# SRAM_MODULE_2_0a.net
KiCad netlist of a schematic drawn in EAGLE
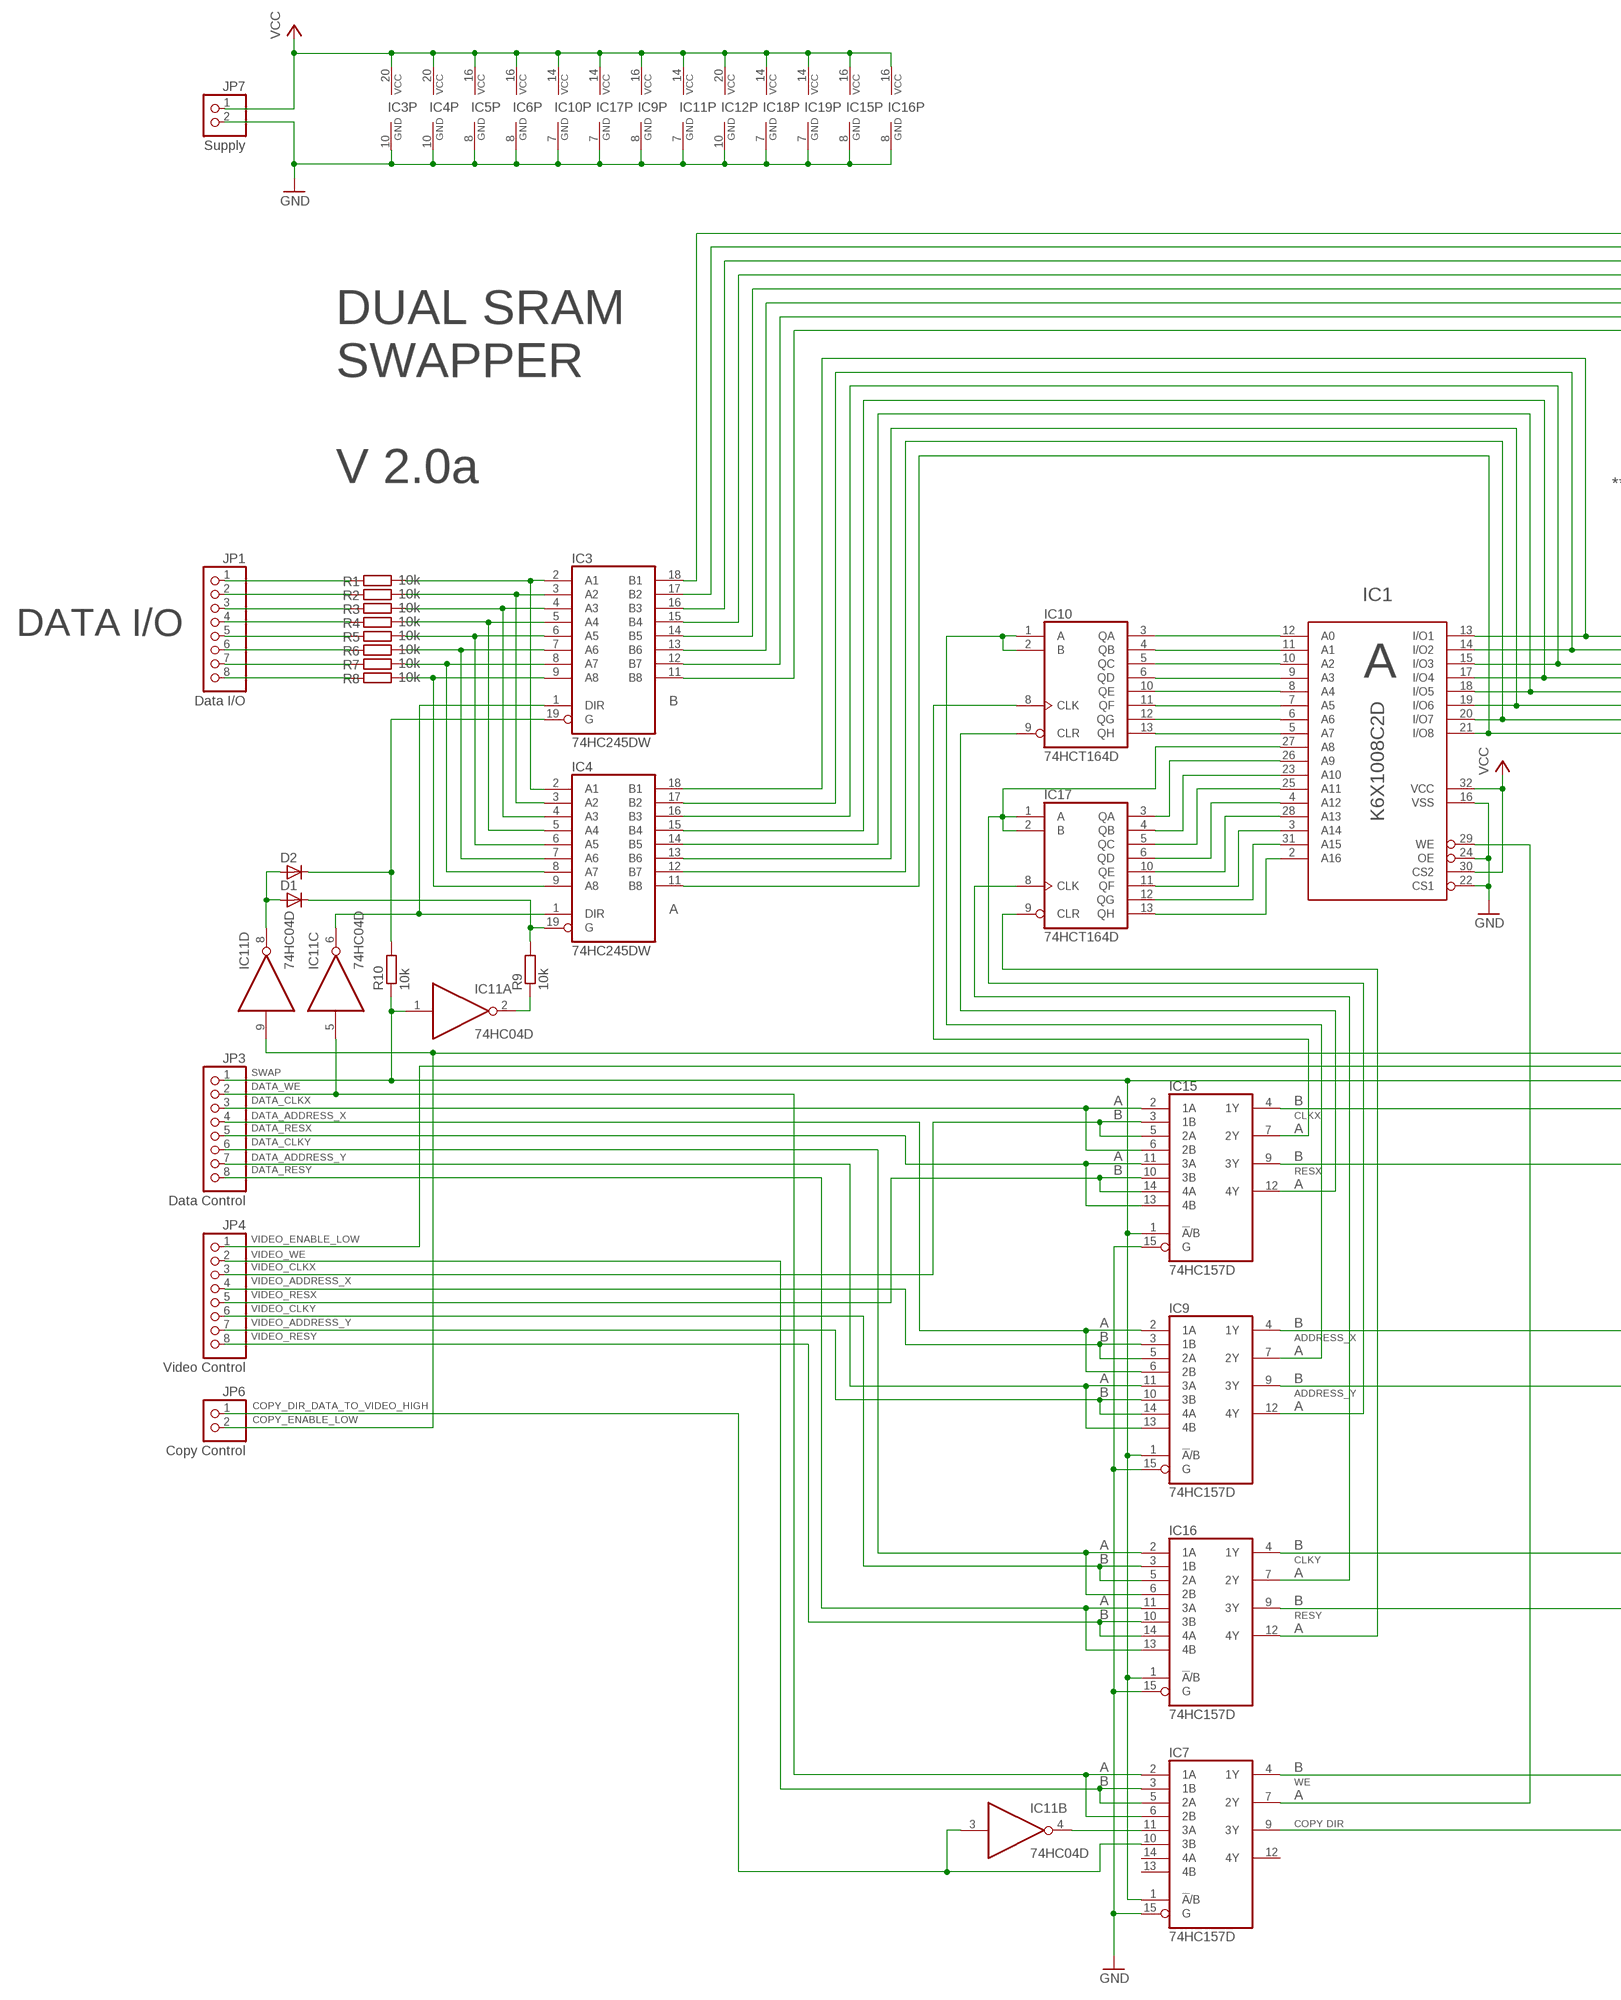
[diagram p0: schematic, sheet 1, part 1 of 2]
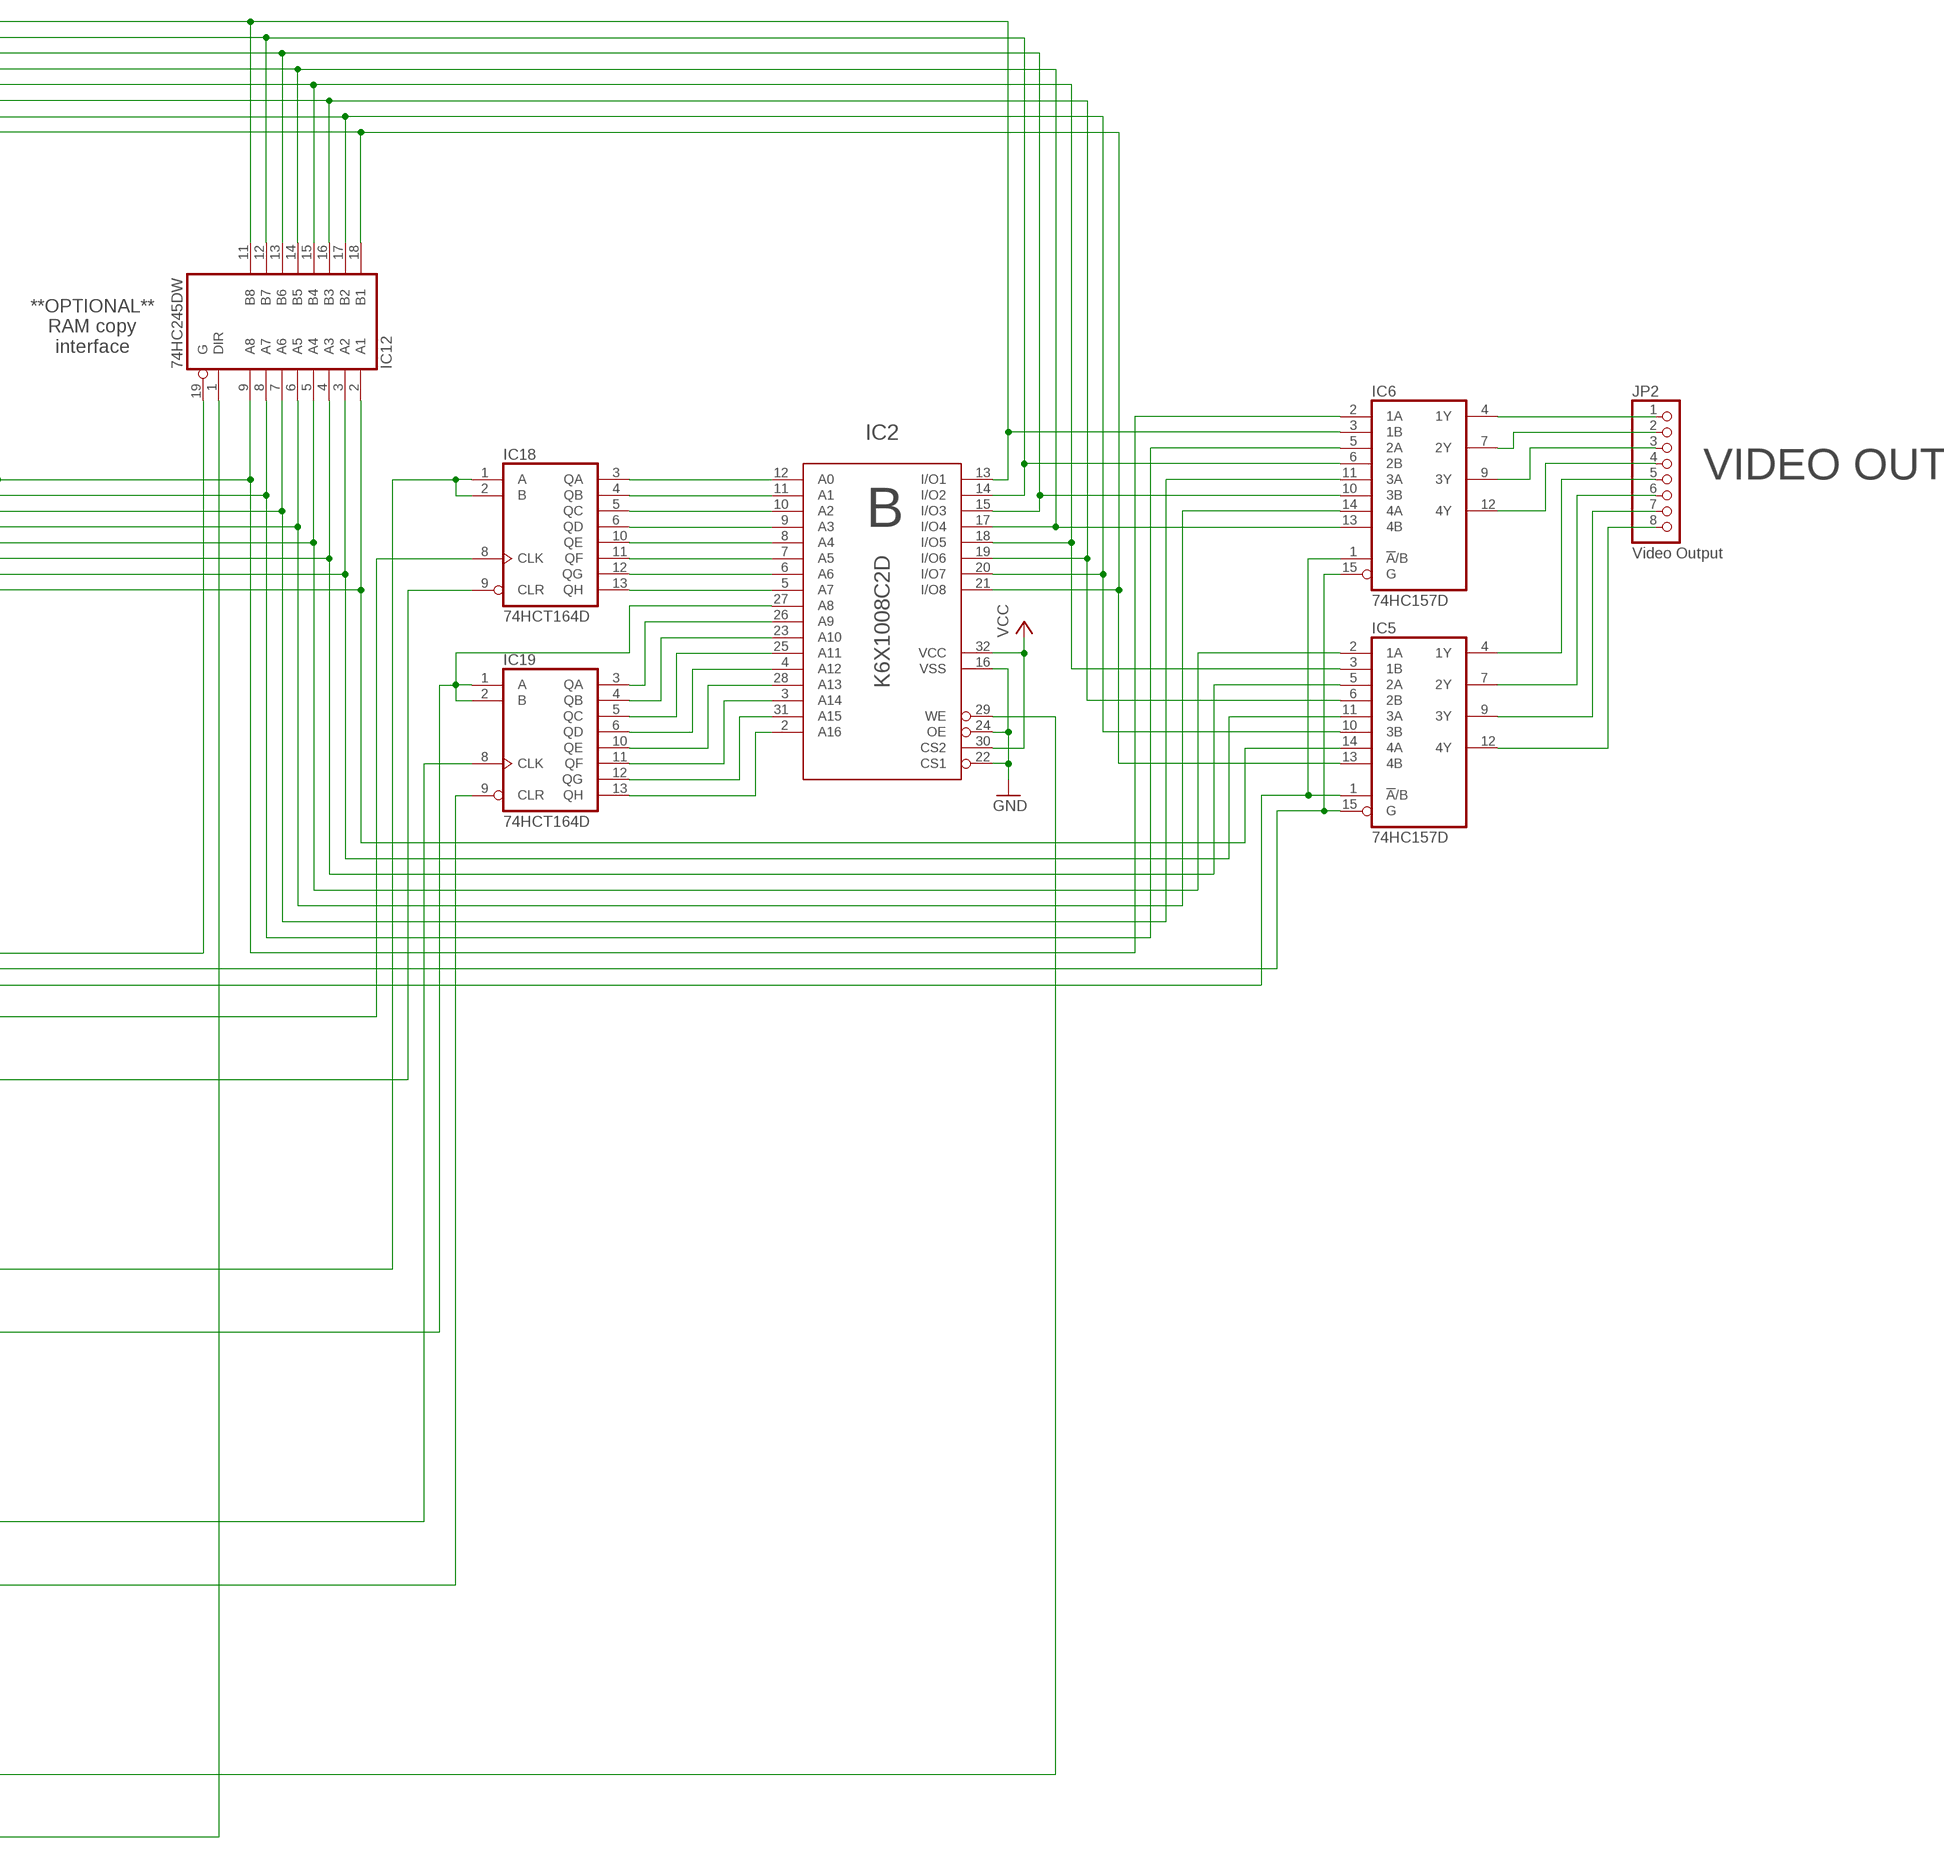
[diagram p1: schematic, sheet 1, part 2 of 2]

(export (version "E")
  (design (tool "Eeschema 10.0.6"))
  (components
    (comp (ref "D1")
      (value "D-A1-C3")
      (footprint "eagle-import:SOT23")
      (libsource (lib "eagle-import") (part "D-A1-C3"))
    )
    (comp (ref "D2")
      (value "D-A1-C3")
      (footprint "eagle-import:SOT23")
      (libsource (lib "eagle-import") (part "D-A1-C3"))
    )
    (comp (ref "IC1")
      (value "K6X1008C2D")
      (footprint "eagle-import:SOP32-5")
      (libsource (lib "eagle-import") (part "K6X1008C2D"))
    )
    (comp (ref "IC2")
      (value "K6X1008C2D")
      (footprint "eagle-import:SOP32-5")
      (libsource (lib "eagle-import") (part "K6X1008C2D"))
    )
    (comp (ref "IC3")
      (value "74HC245DW")
      (footprint "eagle-import:SO20W")
      (libsource (lib "eagle-import") (part "74245DWHC"))
    )
    (comp (ref "IC4")
      (value "74HC245DW")
      (footprint "eagle-import:SO20W")
      (libsource (lib "eagle-import") (part "74245DWHC"))
    )
    (comp (ref "IC5")
      (value "74HC157D")
      (footprint "eagle-import:SO16")
      (libsource (lib "eagle-import") (part "74157DHC"))
    )
    (comp (ref "IC6")
      (value "74HC157D")
      (footprint "eagle-import:SO16")
      (libsource (lib "eagle-import") (part "74157DHC"))
    )
    (comp (ref "IC7")
      (value "74HC157D")
      (footprint "eagle-import:SO16")
      (libsource (lib "eagle-import") (part "74157DHC"))
    )
    (comp (ref "IC9")
      (value "74HC157D")
      (footprint "eagle-import:SO16")
      (libsource (lib "eagle-import") (part "74157DHC"))
    )
    (comp (ref "IC10")
      (value "74HCT164D")
      (footprint "eagle-import:SO14")
      (libsource (lib "eagle-import") (part "74164DHCT"))
    )
    (comp (ref "IC11")
      (value "74HC04D")
      (footprint "eagle-import:SO14")
      (libsource (lib "eagle-import") (part "7404DHC"))
    )
    (comp (ref "IC12")
      (value "74HC245DW")
      (footprint "eagle-import:SO20W")
      (libsource (lib "eagle-import") (part "74245DWHC"))
    )
    (comp (ref "IC15")
      (value "74HC157D")
      (footprint "eagle-import:SO16")
      (libsource (lib "eagle-import") (part "74157DHC"))
    )
    (comp (ref "IC16")
      (value "74HC157D")
      (footprint "eagle-import:SO16")
      (libsource (lib "eagle-import") (part "74157DHC"))
    )
    (comp (ref "IC17")
      (value "74HCT164D")
      (footprint "eagle-import:SO14")
      (libsource (lib "eagle-import") (part "74164DHCT"))
    )
    (comp (ref "IC18")
      (value "74HCT164D")
      (footprint "eagle-import:SO14")
      (libsource (lib "eagle-import") (part "74164DHCT"))
    )
    (comp (ref "IC19")
      (value "74HCT164D")
      (footprint "eagle-import:SO14")
      (libsource (lib "eagle-import") (part "74164DHCT"))
    )
    (comp (ref "JP1")
      (value "Data I/O")
      (footprint "eagle-import:1X08")
      (libsource (lib "eagle-import") (part "PINHD-1X8"))
    )
    (comp (ref "JP2")
      (value "Video Output")
      (footprint "eagle-import:1X08")
      (libsource (lib "eagle-import") (part "PINHD-1X8"))
    )
    (comp (ref "JP3")
      (value "Data Control")
      (footprint "eagle-import:1X08")
      (libsource (lib "eagle-import") (part "PINHD-1X8"))
    )
    (comp (ref "JP4")
      (value "Video Control")
      (footprint "eagle-import:1X08")
      (libsource (lib "eagle-import") (part "PINHD-1X8"))
    )
    (comp (ref "JP6")
      (value "Copy Control")
      (footprint "eagle-import:1X02")
      (libsource (lib "eagle-import") (part "PINHD-1X2"))
    )
    (comp (ref "JP7")
      (value "Supply")
      (footprint "eagle-import:1X02")
      (libsource (lib "eagle-import") (part "PINHD-1X2"))
    )
    (comp (ref "R1")
      (value "10k")
      (footprint "eagle-import:R0603")
      (libsource (lib "eagle-import") (part "R-EU_R0603"))
    )
    (comp (ref "R2")
      (value "10k")
      (footprint "eagle-import:R0603")
      (libsource (lib "eagle-import") (part "R-EU_R0603"))
    )
    (comp (ref "R3")
      (value "10k")
      (footprint "eagle-import:R0603")
      (libsource (lib "eagle-import") (part "R-EU_R0603"))
    )
    (comp (ref "R4")
      (value "10k")
      (footprint "eagle-import:R0603")
      (libsource (lib "eagle-import") (part "R-EU_R0603"))
    )
    (comp (ref "R5")
      (value "10k")
      (footprint "eagle-import:R0603")
      (libsource (lib "eagle-import") (part "R-EU_R0603"))
    )
    (comp (ref "R6")
      (value "10k")
      (footprint "eagle-import:R0603")
      (libsource (lib "eagle-import") (part "R-EU_R0603"))
    )
    (comp (ref "R7")
      (value "10k")
      (footprint "eagle-import:R0603")
      (libsource (lib "eagle-import") (part "R-EU_R0603"))
    )
    (comp (ref "R8")
      (value "10k")
      (footprint "eagle-import:R0603")
      (libsource (lib "eagle-import") (part "R-EU_R0603"))
    )
    (comp (ref "R9")
      (value "10k")
      (footprint "eagle-import:R0603")
      (libsource (lib "eagle-import") (part "R-EU_R0603"))
    )
    (comp (ref "R10")
      (value "10k")
      (footprint "eagle-import:R0603")
      (libsource (lib "eagle-import") (part "R-EU_R0603"))
    )
  )
  (nets
    (net (code "1") (name "/COPY_DIR_DATA_TO_VIDEO_HIGH") (class "Default")
      (node (ref "IC11") (pin "3") (pinfunction "I_3") (pintype "input"))
      (node (ref "IC7") (pin "10") (pinfunction "3B_10") (pintype "input"))
      (node (ref "JP6") (pin "1") (pinfunction "1_1") (pintype "passive"))
    )
    (net (code "2") (name "/COPY_ENABLE_LOW") (class "Default")
      (node (ref "IC11") (pin "9") (pinfunction "I_9") (pintype "input"))
      (node (ref "IC12") (pin "19") (pinfunction "G_19") (pintype "input"))
      (node (ref "JP6") (pin "2") (pinfunction "2_2") (pintype "passive"))
    )
    (net (code "3") (name "/DATA_ADDRESS_X") (class "Default")
      (node (ref "IC9") (pin "2") (pinfunction "1A_2") (pintype "input"))
      (node (ref "IC9") (pin "6") (pinfunction "2B_6") (pintype "input"))
      (node (ref "JP3") (pin "4") (pinfunction "4_4") (pintype "passive"))
    )
    (net (code "4") (name "/DATA_ADDRESS_Y") (class "Default")
      (node (ref "IC9") (pin "11") (pinfunction "3A_11") (pintype "input"))
      (node (ref "IC9") (pin "13") (pinfunction "4B_13") (pintype "input"))
      (node (ref "JP3") (pin "7") (pinfunction "7_7") (pintype "passive"))
    )
    (net (code "5") (name "/DATA_CLKX") (class "Default")
      (node (ref "IC15") (pin "2") (pinfunction "1A_2") (pintype "input"))
      (node (ref "IC15") (pin "6") (pinfunction "2B_6") (pintype "input"))
      (node (ref "JP3") (pin "3") (pinfunction "3_3") (pintype "passive"))
    )
    (net (code "6") (name "/DATA_CLKY") (class "Default")
      (node (ref "IC16") (pin "2") (pinfunction "1A_2") (pintype "input"))
      (node (ref "IC16") (pin "6") (pinfunction "2B_6") (pintype "input"))
      (node (ref "JP3") (pin "6") (pinfunction "6_6") (pintype "passive"))
    )
    (net (code "7") (name "/DATA_RESX") (class "Default")
      (node (ref "IC15") (pin "11") (pinfunction "3A_11") (pintype "input"))
      (node (ref "IC15") (pin "13") (pinfunction "4B_13") (pintype "input"))
      (node (ref "JP3") (pin "5") (pinfunction "5_5") (pintype "passive"))
    )
    (net (code "8") (name "/DATA_RESY") (class "Default")
      (node (ref "IC16") (pin "11") (pinfunction "3A_11") (pintype "input"))
      (node (ref "IC16") (pin "13") (pinfunction "4B_13") (pintype "input"))
      (node (ref "JP3") (pin "8") (pinfunction "8_8") (pintype "passive"))
    )
    (net (code "9") (name "/DATA_WE") (class "Default")
      (node (ref "IC11") (pin "5") (pinfunction "I_5") (pintype "input"))
      (node (ref "IC7") (pin "2") (pinfunction "1A_2") (pintype "input"))
      (node (ref "IC7") (pin "6") (pinfunction "2B_6") (pintype "input"))
      (node (ref "JP3") (pin "2") (pinfunction "2_2") (pintype "passive"))
    )
    (net (code "10") (name "/SWAP") (class "Default")
      (node (ref "IC11") (pin "1") (pinfunction "I_1") (pintype "input"))
      (node (ref "IC15") (pin "1") (pinfunction "~{A}/B_1") (pintype "input"))
      (node (ref "IC16") (pin "1") (pinfunction "~{A}/B_1") (pintype "input"))
      (node (ref "IC5") (pin "1") (pinfunction "~{A}/B_1") (pintype "input"))
      (node (ref "IC6") (pin "1") (pinfunction "~{A}/B_1") (pintype "input"))
      (node (ref "IC7") (pin "1") (pinfunction "~{A}/B_1") (pintype "input"))
      (node (ref "IC9") (pin "1") (pinfunction "~{A}/B_1") (pintype "input"))
      (node (ref "JP3") (pin "1") (pinfunction "1_1") (pintype "passive"))
      (node (ref "R10") (pin "1") (pinfunction "1_1") (pintype "passive"))
    )
    (net (code "11") (name "/VIDEO_ADDRESS_X") (class "Default")
      (node (ref "IC9") (pin "3") (pinfunction "1B_3") (pintype "input"))
      (node (ref "IC9") (pin "5") (pinfunction "2A_5") (pintype "input"))
      (node (ref "JP4") (pin "4") (pinfunction "4_4") (pintype "passive"))
    )
    (net (code "12") (name "/VIDEO_ADDRESS_Y") (class "Default")
      (node (ref "IC9") (pin "10") (pinfunction "3B_10") (pintype "input"))
      (node (ref "IC9") (pin "14") (pinfunction "4A_14") (pintype "input"))
      (node (ref "JP4") (pin "7") (pinfunction "7_7") (pintype "passive"))
    )
    (net (code "13") (name "/VIDEO_CLKX") (class "Default")
      (node (ref "IC15") (pin "3") (pinfunction "1B_3") (pintype "input"))
      (node (ref "IC15") (pin "5") (pinfunction "2A_5") (pintype "input"))
      (node (ref "JP4") (pin "3") (pinfunction "3_3") (pintype "passive"))
    )
    (net (code "14") (name "/VIDEO_CLKY") (class "Default")
      (node (ref "IC16") (pin "3") (pinfunction "1B_3") (pintype "input"))
      (node (ref "IC16") (pin "5") (pinfunction "2A_5") (pintype "input"))
      (node (ref "JP4") (pin "6") (pinfunction "6_6") (pintype "passive"))
    )
    (net (code "15") (name "/VIDEO_ENABLE_LOW") (class "Default")
      (node (ref "IC5") (pin "15") (pinfunction "G_15") (pintype "input"))
      (node (ref "IC6") (pin "15") (pinfunction "G_15") (pintype "input"))
      (node (ref "JP4") (pin "1") (pinfunction "1_1") (pintype "passive"))
    )
    (net (code "16") (name "/VIDEO_RESX") (class "Default")
      (node (ref "IC15") (pin "10") (pinfunction "3B_10") (pintype "input"))
      (node (ref "IC15") (pin "14") (pinfunction "4A_14") (pintype "input"))
      (node (ref "JP4") (pin "5") (pinfunction "5_5") (pintype "passive"))
    )
    (net (code "17") (name "/VIDEO_RESY") (class "Default")
      (node (ref "IC16") (pin "10") (pinfunction "3B_10") (pintype "input"))
      (node (ref "IC16") (pin "14") (pinfunction "4A_14") (pintype "input"))
      (node (ref "JP4") (pin "8") (pinfunction "8_8") (pintype "passive"))
    )
    (net (code "18") (name "/VIDEO_WE") (class "Default")
      (node (ref "IC7") (pin "3") (pinfunction "1B_3") (pintype "input"))
      (node (ref "IC7") (pin "5") (pinfunction "2A_5") (pintype "input"))
      (node (ref "JP4") (pin "2") (pinfunction "2_2") (pintype "passive"))
    )
    (net (code "19") (name "GND") (class "Default")
      (node (ref "IC1") (pin "16") (pinfunction "VSS_16") (pintype "power_in"))
      (node (ref "IC1") (pin "22") (pinfunction "CS1_22") (pintype "input"))
      (node (ref "IC1") (pin "24") (pinfunction "OE_24") (pintype "input"))
      (node (ref "IC10") (pin "7") (pinfunction "GND_7") (pintype "power_in"))
      (node (ref "IC11") (pin "7") (pinfunction "GND_7") (pintype "power_in"))
      (node (ref "IC12") (pin "10") (pinfunction "GND_10") (pintype "power_in"))
      (node (ref "IC15") (pin "15") (pinfunction "G_15") (pintype "input"))
      (node (ref "IC15") (pin "8") (pinfunction "GND_8") (pintype "power_in"))
      (node (ref "IC16") (pin "15") (pinfunction "G_15") (pintype "input"))
      (node (ref "IC16") (pin "8") (pinfunction "GND_8") (pintype "power_in"))
      (node (ref "IC17") (pin "7") (pinfunction "GND_7") (pintype "power_in"))
      (node (ref "IC18") (pin "7") (pinfunction "GND_7") (pintype "power_in"))
      (node (ref "IC19") (pin "7") (pinfunction "GND_7") (pintype "power_in"))
      (node (ref "IC2") (pin "16") (pinfunction "VSS_16") (pintype "power_in"))
      (node (ref "IC2") (pin "22") (pinfunction "CS1_22") (pintype "input"))
      (node (ref "IC2") (pin "24") (pinfunction "OE_24") (pintype "input"))
      (node (ref "IC3") (pin "10") (pinfunction "GND_10") (pintype "power_in"))
      (node (ref "IC4") (pin "10") (pinfunction "GND_10") (pintype "power_in"))
      (node (ref "IC5") (pin "8") (pinfunction "GND_8") (pintype "power_in"))
      (node (ref "IC6") (pin "8") (pinfunction "GND_8") (pintype "power_in"))
      (node (ref "IC7") (pin "15") (pinfunction "G_15") (pintype "input"))
      (node (ref "IC9") (pin "15") (pinfunction "G_15") (pintype "input"))
      (node (ref "IC9") (pin "8") (pinfunction "GND_8") (pintype "power_in"))
      (node (ref "JP7") (pin "2") (pinfunction "2_2") (pintype "passive"))
    )
    (net (code "20") (name "Net-(D1-A)") (class "Default")
      (node (ref "D1") (pin "1") (pinfunction "A_1") (pintype "passive"))
      (node (ref "D2") (pin "1") (pinfunction "A_1") (pintype "passive"))
      (node (ref "IC11") (pin "8") (pinfunction "O_8") (pintype "output"))
    )
    (net (code "21") (name "Net-(D1-C)") (class "Default")
      (node (ref "D1") (pin "3") (pinfunction "C_3") (pintype "passive"))
      (node (ref "IC4") (pin "19") (pinfunction "G_19") (pintype "input"))
      (node (ref "R9") (pin "2") (pinfunction "2_2") (pintype "passive"))
    )
    (net (code "22") (name "Net-(D2-C)") (class "Default")
      (node (ref "D2") (pin "3") (pinfunction "C_3") (pintype "passive"))
      (node (ref "IC3") (pin "19") (pinfunction "G_19") (pintype "input"))
      (node (ref "R10") (pin "2") (pinfunction "2_2") (pintype "passive"))
    )
    (net (code "23") (name "Net-(IC1-A0)") (class "Default")
      (node (ref "IC1") (pin "12") (pinfunction "A0_12") (pintype "input"))
      (node (ref "IC10") (pin "3") (pinfunction "QA_3") (pintype "output"))
    )
    (net (code "24") (name "Net-(IC1-A1)") (class "Default")
      (node (ref "IC1") (pin "11") (pinfunction "A1_11") (pintype "input"))
      (node (ref "IC10") (pin "4") (pinfunction "QB_4") (pintype "output"))
    )
    (net (code "25") (name "Net-(IC1-A2)") (class "Default")
      (node (ref "IC1") (pin "10") (pinfunction "A2_10") (pintype "input"))
      (node (ref "IC10") (pin "5") (pinfunction "QC_5") (pintype "output"))
    )
    (net (code "26") (name "Net-(IC1-A3)") (class "Default")
      (node (ref "IC1") (pin "9") (pinfunction "A3_9") (pintype "input"))
      (node (ref "IC10") (pin "6") (pinfunction "QD_6") (pintype "output"))
    )
    (net (code "27") (name "Net-(IC1-A4)") (class "Default")
      (node (ref "IC1") (pin "8") (pinfunction "A4_8") (pintype "input"))
      (node (ref "IC10") (pin "10") (pinfunction "QE_10") (pintype "output"))
    )
    (net (code "28") (name "Net-(IC1-A5)") (class "Default")
      (node (ref "IC1") (pin "7") (pinfunction "A5_7") (pintype "input"))
      (node (ref "IC10") (pin "11") (pinfunction "QF_11") (pintype "output"))
    )
    (net (code "29") (name "Net-(IC1-A6)") (class "Default")
      (node (ref "IC1") (pin "6") (pinfunction "A6_6") (pintype "input"))
      (node (ref "IC10") (pin "12") (pinfunction "QG_12") (pintype "output"))
    )
    (net (code "30") (name "Net-(IC1-A7)") (class "Default")
      (node (ref "IC1") (pin "5") (pinfunction "A7_5") (pintype "input"))
      (node (ref "IC10") (pin "13") (pinfunction "QH_13") (pintype "output"))
    )
    (net (code "31") (name "Net-(IC1-A8)") (class "Default")
      (node (ref "IC1") (pin "27") (pinfunction "A8_27") (pintype "input"))
      (node (ref "IC17") (pin "1") (pinfunction "A_1") (pintype "input"))
      (node (ref "IC17") (pin "2") (pinfunction "B_2") (pintype "input"))
      (node (ref "IC9") (pin "12") (pinfunction "4Y_12") (pintype "output"))
    )
    (net (code "32") (name "Net-(IC1-A9)") (class "Default")
      (node (ref "IC1") (pin "26") (pinfunction "A9_26") (pintype "input"))
      (node (ref "IC17") (pin "3") (pinfunction "QA_3") (pintype "output"))
    )
    (net (code "33") (name "Net-(IC1-A10)") (class "Default")
      (node (ref "IC1") (pin "23") (pinfunction "A10_23") (pintype "input"))
      (node (ref "IC17") (pin "4") (pinfunction "QB_4") (pintype "output"))
    )
    (net (code "34") (name "Net-(IC1-A11)") (class "Default")
      (node (ref "IC1") (pin "25") (pinfunction "A11_25") (pintype "input"))
      (node (ref "IC17") (pin "5") (pinfunction "QC_5") (pintype "output"))
    )
    (net (code "35") (name "Net-(IC1-A12)") (class "Default")
      (node (ref "IC1") (pin "4") (pinfunction "A12_4") (pintype "input"))
      (node (ref "IC17") (pin "6") (pinfunction "QD_6") (pintype "output"))
    )
    (net (code "36") (name "Net-(IC1-A13)") (class "Default")
      (node (ref "IC1") (pin "28") (pinfunction "A13_28") (pintype "input"))
      (node (ref "IC17") (pin "10") (pinfunction "QE_10") (pintype "output"))
    )
    (net (code "37") (name "Net-(IC1-A14)") (class "Default")
      (node (ref "IC1") (pin "3") (pinfunction "A14_3") (pintype "input"))
      (node (ref "IC17") (pin "11") (pinfunction "QF_11") (pintype "output"))
    )
    (net (code "38") (name "Net-(IC1-A15)") (class "Default")
      (node (ref "IC1") (pin "31") (pinfunction "A15_31") (pintype "input"))
      (node (ref "IC17") (pin "12") (pinfunction "QG_12") (pintype "output"))
    )
    (net (code "39") (name "Net-(IC1-A16)") (class "Default")
      (node (ref "IC1") (pin "2") (pinfunction "A16_2") (pintype "input"))
      (node (ref "IC17") (pin "13") (pinfunction "QH_13") (pintype "output"))
    )
    (net (code "40") (name "Net-(IC1-I{slash}O1)") (class "Default")
      (node (ref "IC1") (pin "13") (pinfunction "I/O1_13") (pintype "bidirectional"))
      (node (ref "IC12") (pin "9") (pinfunction "A8_9") (pintype "bidirectional"))
      (node (ref "IC4") (pin "18") (pinfunction "B1_18") (pintype "bidirectional"))
      (node (ref "IC6") (pin "2") (pinfunction "1A_2") (pintype "input"))
    )
    (net (code "41") (name "Net-(IC1-I{slash}O2)") (class "Default")
      (node (ref "IC1") (pin "14") (pinfunction "I/O2_14") (pintype "bidirectional"))
      (node (ref "IC12") (pin "8") (pinfunction "A7_8") (pintype "bidirectional"))
      (node (ref "IC4") (pin "17") (pinfunction "B2_17") (pintype "bidirectional"))
      (node (ref "IC6") (pin "5") (pinfunction "2A_5") (pintype "input"))
    )
    (net (code "42") (name "Net-(IC1-I{slash}O3)") (class "Default")
      (node (ref "IC1") (pin "15") (pinfunction "I/O3_15") (pintype "bidirectional"))
      (node (ref "IC12") (pin "7") (pinfunction "A6_7") (pintype "bidirectional"))
      (node (ref "IC4") (pin "16") (pinfunction "B3_16") (pintype "bidirectional"))
      (node (ref "IC6") (pin "11") (pinfunction "3A_11") (pintype "input"))
    )
    (net (code "43") (name "Net-(IC1-I{slash}O4)") (class "Default")
      (node (ref "IC1") (pin "17") (pinfunction "I/O4_17") (pintype "bidirectional"))
      (node (ref "IC12") (pin "6") (pinfunction "A5_6") (pintype "bidirectional"))
      (node (ref "IC4") (pin "15") (pinfunction "B4_15") (pintype "bidirectional"))
      (node (ref "IC6") (pin "14") (pinfunction "4A_14") (pintype "input"))
    )
    (net (code "44") (name "Net-(IC1-I{slash}O5)") (class "Default")
      (node (ref "IC1") (pin "18") (pinfunction "I/O5_18") (pintype "bidirectional"))
      (node (ref "IC12") (pin "5") (pinfunction "A4_5") (pintype "bidirectional"))
      (node (ref "IC4") (pin "14") (pinfunction "B5_14") (pintype "bidirectional"))
      (node (ref "IC5") (pin "2") (pinfunction "1A_2") (pintype "input"))
    )
    (net (code "45") (name "Net-(IC1-I{slash}O6)") (class "Default")
      (node (ref "IC1") (pin "19") (pinfunction "I/O6_19") (pintype "bidirectional"))
      (node (ref "IC12") (pin "4") (pinfunction "A3_4") (pintype "bidirectional"))
      (node (ref "IC4") (pin "13") (pinfunction "B6_13") (pintype "bidirectional"))
      (node (ref "IC5") (pin "5") (pinfunction "2A_5") (pintype "input"))
    )
    (net (code "46") (name "Net-(IC1-I{slash}O7)") (class "Default")
      (node (ref "IC1") (pin "20") (pinfunction "I/O7_20") (pintype "bidirectional"))
      (node (ref "IC12") (pin "3") (pinfunction "A2_3") (pintype "bidirectional"))
      (node (ref "IC4") (pin "12") (pinfunction "B7_12") (pintype "bidirectional"))
      (node (ref "IC5") (pin "11") (pinfunction "3A_11") (pintype "input"))
    )
    (net (code "47") (name "Net-(IC1-I{slash}O8)") (class "Default")
      (node (ref "IC1") (pin "21") (pinfunction "I/O8_21") (pintype "bidirectional"))
      (node (ref "IC12") (pin "2") (pinfunction "A1_2") (pintype "bidirectional"))
      (node (ref "IC4") (pin "11") (pinfunction "B8_11") (pintype "bidirectional"))
      (node (ref "IC5") (pin "14") (pinfunction "4A_14") (pintype "input"))
    )
    (net (code "48") (name "Net-(IC1-WE)") (class "Default")
      (node (ref "IC1") (pin "29") (pinfunction "WE_29") (pintype "input"))
      (node (ref "IC7") (pin "7") (pinfunction "2Y_7") (pintype "output"))
    )
    (net (code "49") (name "Net-(IC2-WE)") (class "Default")
      (node (ref "IC2") (pin "29") (pinfunction "WE_29") (pintype "input"))
      (node (ref "IC7") (pin "4") (pinfunction "1Y_4") (pintype "output"))
    )
    (net (code "50") (name "Net-(IC3A-A1)") (class "Default")
      (node (ref "IC3") (pin "2") (pinfunction "A1_2") (pintype "bidirectional"))
      (node (ref "IC4") (pin "2") (pinfunction "A1_2") (pintype "bidirectional"))
      (node (ref "R1") (pin "2") (pinfunction "2_2") (pintype "passive"))
    )
    (net (code "51") (name "Net-(IC3A-A2)") (class "Default")
      (node (ref "IC3") (pin "3") (pinfunction "A2_3") (pintype "bidirectional"))
      (node (ref "IC4") (pin "3") (pinfunction "A2_3") (pintype "bidirectional"))
      (node (ref "R2") (pin "2") (pinfunction "2_2") (pintype "passive"))
    )
    (net (code "52") (name "Net-(IC3A-A3)") (class "Default")
      (node (ref "IC3") (pin "4") (pinfunction "A3_4") (pintype "bidirectional"))
      (node (ref "IC4") (pin "4") (pinfunction "A3_4") (pintype "bidirectional"))
      (node (ref "R3") (pin "2") (pinfunction "2_2") (pintype "passive"))
    )
    (net (code "53") (name "Net-(IC3A-A4)") (class "Default")
      (node (ref "IC3") (pin "5") (pinfunction "A4_5") (pintype "bidirectional"))
      (node (ref "IC4") (pin "5") (pinfunction "A4_5") (pintype "bidirectional"))
      (node (ref "R4") (pin "2") (pinfunction "2_2") (pintype "passive"))
    )
    (net (code "54") (name "Net-(IC3A-A5)") (class "Default")
      (node (ref "IC3") (pin "6") (pinfunction "A5_6") (pintype "bidirectional"))
      (node (ref "IC4") (pin "6") (pinfunction "A5_6") (pintype "bidirectional"))
      (node (ref "R5") (pin "2") (pinfunction "2_2") (pintype "passive"))
    )
    (net (code "55") (name "Net-(IC3A-A6)") (class "Default")
      (node (ref "IC3") (pin "7") (pinfunction "A6_7") (pintype "bidirectional"))
      (node (ref "IC4") (pin "7") (pinfunction "A6_7") (pintype "bidirectional"))
      (node (ref "R6") (pin "2") (pinfunction "2_2") (pintype "passive"))
    )
    (net (code "56") (name "Net-(IC3A-A7)") (class "Default")
      (node (ref "IC3") (pin "8") (pinfunction "A7_8") (pintype "bidirectional"))
      (node (ref "IC4") (pin "8") (pinfunction "A7_8") (pintype "bidirectional"))
      (node (ref "R7") (pin "2") (pinfunction "2_2") (pintype "passive"))
    )
    (net (code "57") (name "Net-(IC3A-A8)") (class "Default")
      (node (ref "IC3") (pin "9") (pinfunction "A8_9") (pintype "bidirectional"))
      (node (ref "IC4") (pin "9") (pinfunction "A8_9") (pintype "bidirectional"))
      (node (ref "R8") (pin "2") (pinfunction "2_2") (pintype "passive"))
    )
    (net (code "58") (name "Net-(IC5A-1Y)") (class "Default")
      (node (ref "IC5") (pin "4") (pinfunction "1Y_4") (pintype "output"))
      (node (ref "JP2") (pin "5") (pinfunction "5_5") (pintype "passive"))
    )
    (net (code "59") (name "Net-(IC5A-2Y)") (class "Default")
      (node (ref "IC5") (pin "7") (pinfunction "2Y_7") (pintype "output"))
      (node (ref "JP2") (pin "6") (pinfunction "6_6") (pintype "passive"))
    )
    (net (code "60") (name "Net-(IC5A-3Y)") (class "Default")
      (node (ref "IC5") (pin "9") (pinfunction "3Y_9") (pintype "output"))
      (node (ref "JP2") (pin "7") (pinfunction "7_7") (pintype "passive"))
    )
    (net (code "61") (name "Net-(IC5A-4Y)") (class "Default")
      (node (ref "IC5") (pin "12") (pinfunction "4Y_12") (pintype "output"))
      (node (ref "JP2") (pin "8") (pinfunction "8_8") (pintype "passive"))
    )
    (net (code "62") (name "Net-(IC6A-1Y)") (class "Default")
      (node (ref "IC6") (pin "4") (pinfunction "1Y_4") (pintype "output"))
      (node (ref "JP2") (pin "1") (pinfunction "1_1") (pintype "passive"))
    )
    (net (code "63") (name "Net-(IC6A-2Y)") (class "Default")
      (node (ref "IC6") (pin "7") (pinfunction "2Y_7") (pintype "output"))
      (node (ref "JP2") (pin "2") (pinfunction "2_2") (pintype "passive"))
    )
    (net (code "64") (name "Net-(IC6A-3Y)") (class "Default")
      (node (ref "IC6") (pin "9") (pinfunction "3Y_9") (pintype "output"))
      (node (ref "JP2") (pin "3") (pinfunction "3_3") (pintype "passive"))
    )
    (net (code "65") (name "Net-(IC6A-4Y)") (class "Default")
      (node (ref "IC6") (pin "12") (pinfunction "4Y_12") (pintype "output"))
      (node (ref "JP2") (pin "4") (pinfunction "4_4") (pintype "passive"))
    )
    (net (code "66") (name "Net-(IC10A-A)") (class "Default")
      (node (ref "IC10") (pin "1") (pinfunction "A_1") (pintype "input"))
      (node (ref "IC10") (pin "2") (pinfunction "B_2") (pintype "input"))
      (node (ref "IC9") (pin "7") (pinfunction "2Y_7") (pintype "output"))
    )
    (net (code "67") (name "Net-(IC10A-CLK)") (class "Default")
      (node (ref "IC10") (pin "8") (pinfunction "CLK_8") (pintype "input"))
      (node (ref "IC15") (pin "7") (pinfunction "2Y_7") (pintype "output"))
    )
    (net (code "68") (name "Net-(IC10A-CLR)") (class "Default")
      (node (ref "IC10") (pin "9") (pinfunction "CLR_9") (pintype "input"))
      (node (ref "IC15") (pin "12") (pinfunction "4Y_12") (pintype "output"))
    )
    (net (code "69") (name "Net-(IC11A-O)") (class "Default")
      (node (ref "IC11") (pin "2") (pinfunction "O_2") (pintype "output"))
      (node (ref "R9") (pin "1") (pinfunction "1_1") (pintype "passive"))
    )
    (net (code "70") (name "Net-(IC11B-O)") (class "Default")
      (node (ref "IC11") (pin "4") (pinfunction "O_4") (pintype "output"))
      (node (ref "IC7") (pin "11") (pinfunction "3A_11") (pintype "input"))
    )
    (net (code "71") (name "Net-(IC11C-O)") (class "Default")
      (node (ref "IC11") (pin "6") (pinfunction "O_6") (pintype "output"))
      (node (ref "IC3") (pin "1") (pinfunction "DIR_1") (pintype "input"))
      (node (ref "IC4") (pin "1") (pinfunction "DIR_1") (pintype "input"))
    )
    (net (code "72") (name "Net-(IC12A-B1)") (class "Default")
      (node (ref "IC12") (pin "18") (pinfunction "B1_18") (pintype "bidirectional"))
      (node (ref "IC2") (pin "21") (pinfunction "I/O8_21") (pintype "bidirectional"))
      (node (ref "IC3") (pin "11") (pinfunction "B8_11") (pintype "bidirectional"))
      (node (ref "IC5") (pin "13") (pinfunction "4B_13") (pintype "input"))
    )
    (net (code "73") (name "Net-(IC12A-B2)") (class "Default")
      (node (ref "IC12") (pin "17") (pinfunction "B2_17") (pintype "bidirectional"))
      (node (ref "IC2") (pin "20") (pinfunction "I/O7_20") (pintype "bidirectional"))
      (node (ref "IC3") (pin "12") (pinfunction "B7_12") (pintype "bidirectional"))
      (node (ref "IC5") (pin "10") (pinfunction "3B_10") (pintype "input"))
    )
    (net (code "74") (name "Net-(IC12A-B3)") (class "Default")
      (node (ref "IC12") (pin "16") (pinfunction "B3_16") (pintype "bidirectional"))
      (node (ref "IC2") (pin "19") (pinfunction "I/O6_19") (pintype "bidirectional"))
      (node (ref "IC3") (pin "13") (pinfunction "B6_13") (pintype "bidirectional"))
      (node (ref "IC5") (pin "6") (pinfunction "2B_6") (pintype "input"))
    )
    (net (code "75") (name "Net-(IC12A-B4)") (class "Default")
      (node (ref "IC12") (pin "15") (pinfunction "B4_15") (pintype "bidirectional"))
      (node (ref "IC2") (pin "18") (pinfunction "I/O5_18") (pintype "bidirectional"))
      (node (ref "IC3") (pin "14") (pinfunction "B5_14") (pintype "bidirectional"))
      (node (ref "IC5") (pin "3") (pinfunction "1B_3") (pintype "input"))
    )
    (net (code "76") (name "Net-(IC12A-B5)") (class "Default")
      (node (ref "IC12") (pin "14") (pinfunction "B5_14") (pintype "bidirectional"))
      (node (ref "IC2") (pin "17") (pinfunction "I/O4_17") (pintype "bidirectional"))
      (node (ref "IC3") (pin "15") (pinfunction "B4_15") (pintype "bidirectional"))
      (node (ref "IC6") (pin "13") (pinfunction "4B_13") (pintype "input"))
    )
    (net (code "77") (name "Net-(IC12A-B6)") (class "Default")
      (node (ref "IC12") (pin "13") (pinfunction "B6_13") (pintype "bidirectional"))
      (node (ref "IC2") (pin "15") (pinfunction "I/O3_15") (pintype "bidirectional"))
      (node (ref "IC3") (pin "16") (pinfunction "B3_16") (pintype "bidirectional"))
      (node (ref "IC6") (pin "10") (pinfunction "3B_10") (pintype "input"))
    )
    (net (code "78") (name "Net-(IC12A-B7)") (class "Default")
      (node (ref "IC12") (pin "12") (pinfunction "B7_12") (pintype "bidirectional"))
      (node (ref "IC2") (pin "14") (pinfunction "I/O2_14") (pintype "bidirectional"))
      (node (ref "IC3") (pin "17") (pinfunction "B2_17") (pintype "bidirectional"))
      (node (ref "IC6") (pin "6") (pinfunction "2B_6") (pintype "input"))
    )
    (net (code "79") (name "Net-(IC12A-B8)") (class "Default")
      (node (ref "IC12") (pin "11") (pinfunction "B8_11") (pintype "bidirectional"))
      (node (ref "IC2") (pin "13") (pinfunction "I/O1_13") (pintype "bidirectional"))
      (node (ref "IC3") (pin "18") (pinfunction "B1_18") (pintype "bidirectional"))
      (node (ref "IC6") (pin "3") (pinfunction "1B_3") (pintype "input"))
    )
    (net (code "80") (name "Net-(IC12A-DIR)") (class "Default")
      (node (ref "IC12") (pin "1") (pinfunction "DIR_1") (pintype "input"))
      (node (ref "IC7") (pin "9") (pinfunction "3Y_9") (pintype "output"))
    )
    (net (code "81") (name "Net-(IC15A-1Y)") (class "Default")
      (node (ref "IC15") (pin "4") (pinfunction "1Y_4") (pintype "output"))
      (node (ref "IC18") (pin "8") (pinfunction "CLK_8") (pintype "input"))
    )
    (net (code "82") (name "Net-(IC15A-3Y)") (class "Default")
      (node (ref "IC15") (pin "9") (pinfunction "3Y_9") (pintype "output"))
      (node (ref "IC18") (pin "9") (pinfunction "CLR_9") (pintype "input"))
    )
    (net (code "83") (name "Net-(IC16A-1Y)") (class "Default")
      (node (ref "IC16") (pin "4") (pinfunction "1Y_4") (pintype "output"))
      (node (ref "IC19") (pin "8") (pinfunction "CLK_8") (pintype "input"))
    )
    (net (code "84") (name "Net-(IC16A-2Y)") (class "Default")
      (node (ref "IC16") (pin "7") (pinfunction "2Y_7") (pintype "output"))
      (node (ref "IC17") (pin "8") (pinfunction "CLK_8") (pintype "input"))
    )
    (net (code "85") (name "Net-(IC16A-3Y)") (class "Default")
      (node (ref "IC16") (pin "9") (pinfunction "3Y_9") (pintype "output"))
      (node (ref "IC19") (pin "9") (pinfunction "CLR_9") (pintype "input"))
    )
    (net (code "86") (name "Net-(IC16A-4Y)") (class "Default")
      (node (ref "IC16") (pin "12") (pinfunction "4Y_12") (pintype "output"))
      (node (ref "IC17") (pin "9") (pinfunction "CLR_9") (pintype "input"))
    )
    (net (code "87") (name "Net-(IC18A-A)") (class "Default")
      (node (ref "IC18") (pin "1") (pinfunction "A_1") (pintype "input"))
      (node (ref "IC18") (pin "2") (pinfunction "B_2") (pintype "input"))
      (node (ref "IC9") (pin "4") (pinfunction "1Y_4") (pintype "output"))
    )
    (net (code "88") (name "Net-(IC18A-QA)") (class "Default")
      (node (ref "IC18") (pin "3") (pinfunction "QA_3") (pintype "output"))
      (node (ref "IC2") (pin "12") (pinfunction "A0_12") (pintype "input"))
    )
    (net (code "89") (name "Net-(IC18A-QB)") (class "Default")
      (node (ref "IC18") (pin "4") (pinfunction "QB_4") (pintype "output"))
      (node (ref "IC2") (pin "11") (pinfunction "A1_11") (pintype "input"))
    )
    (net (code "90") (name "Net-(IC18A-QC)") (class "Default")
      (node (ref "IC18") (pin "5") (pinfunction "QC_5") (pintype "output"))
      (node (ref "IC2") (pin "10") (pinfunction "A2_10") (pintype "input"))
    )
    (net (code "91") (name "Net-(IC18A-QD)") (class "Default")
      (node (ref "IC18") (pin "6") (pinfunction "QD_6") (pintype "output"))
      (node (ref "IC2") (pin "9") (pinfunction "A3_9") (pintype "input"))
    )
    (net (code "92") (name "Net-(IC18A-QE)") (class "Default")
      (node (ref "IC18") (pin "10") (pinfunction "QE_10") (pintype "output"))
      (node (ref "IC2") (pin "8") (pinfunction "A4_8") (pintype "input"))
    )
    (net (code "93") (name "Net-(IC18A-QF)") (class "Default")
      (node (ref "IC18") (pin "11") (pinfunction "QF_11") (pintype "output"))
      (node (ref "IC2") (pin "7") (pinfunction "A5_7") (pintype "input"))
    )
    (net (code "94") (name "Net-(IC18A-QG)") (class "Default")
      (node (ref "IC18") (pin "12") (pinfunction "QG_12") (pintype "output"))
      (node (ref "IC2") (pin "6") (pinfunction "A6_6") (pintype "input"))
    )
    (net (code "95") (name "Net-(IC18A-QH)") (class "Default")
      (node (ref "IC18") (pin "13") (pinfunction "QH_13") (pintype "output"))
      (node (ref "IC2") (pin "5") (pinfunction "A7_5") (pintype "input"))
    )
    (net (code "96") (name "Net-(IC19A-A)") (class "Default")
      (node (ref "IC19") (pin "1") (pinfunction "A_1") (pintype "input"))
      (node (ref "IC19") (pin "2") (pinfunction "B_2") (pintype "input"))
      (node (ref "IC2") (pin "27") (pinfunction "A8_27") (pintype "input"))
      (node (ref "IC9") (pin "9") (pinfunction "3Y_9") (pintype "output"))
    )
    (net (code "97") (name "Net-(IC19A-QA)") (class "Default")
      (node (ref "IC19") (pin "3") (pinfunction "QA_3") (pintype "output"))
      (node (ref "IC2") (pin "26") (pinfunction "A9_26") (pintype "input"))
    )
    (net (code "98") (name "Net-(IC19A-QB)") (class "Default")
      (node (ref "IC19") (pin "4") (pinfunction "QB_4") (pintype "output"))
      (node (ref "IC2") (pin "23") (pinfunction "A10_23") (pintype "input"))
    )
    (net (code "99") (name "Net-(IC19A-QC)") (class "Default")
      (node (ref "IC19") (pin "5") (pinfunction "QC_5") (pintype "output"))
      (node (ref "IC2") (pin "25") (pinfunction "A11_25") (pintype "input"))
    )
    (net (code "100") (name "Net-(IC19A-QD)") (class "Default")
      (node (ref "IC19") (pin "6") (pinfunction "QD_6") (pintype "output"))
      (node (ref "IC2") (pin "4") (pinfunction "A12_4") (pintype "input"))
    )
    (net (code "101") (name "Net-(IC19A-QE)") (class "Default")
      (node (ref "IC19") (pin "10") (pinfunction "QE_10") (pintype "output"))
      (node (ref "IC2") (pin "28") (pinfunction "A13_28") (pintype "input"))
    )
    (net (code "102") (name "Net-(IC19A-QF)") (class "Default")
      (node (ref "IC19") (pin "11") (pinfunction "QF_11") (pintype "output"))
      (node (ref "IC2") (pin "3") (pinfunction "A14_3") (pintype "input"))
    )
    (net (code "103") (name "Net-(IC19A-QG)") (class "Default")
      (node (ref "IC19") (pin "12") (pinfunction "QG_12") (pintype "output"))
      (node (ref "IC2") (pin "31") (pinfunction "A15_31") (pintype "input"))
    )
    (net (code "104") (name "Net-(IC19A-QH)") (class "Default")
      (node (ref "IC19") (pin "13") (pinfunction "QH_13") (pintype "output"))
      (node (ref "IC2") (pin "2") (pinfunction "A16_2") (pintype "input"))
    )
    (net (code "105") (name "Net-(JP1-Pad1)") (class "Default")
      (node (ref "JP1") (pin "1") (pinfunction "1_1") (pintype "passive"))
      (node (ref "R1") (pin "1") (pinfunction "1_1") (pintype "passive"))
    )
    (net (code "106") (name "Net-(JP1-Pad2)") (class "Default")
      (node (ref "JP1") (pin "2") (pinfunction "2_2") (pintype "passive"))
      (node (ref "R2") (pin "1") (pinfunction "1_1") (pintype "passive"))
    )
    (net (code "107") (name "Net-(JP1-Pad3)") (class "Default")
      (node (ref "JP1") (pin "3") (pinfunction "3_3") (pintype "passive"))
      (node (ref "R3") (pin "1") (pinfunction "1_1") (pintype "passive"))
    )
    (net (code "108") (name "Net-(JP1-Pad4)") (class "Default")
      (node (ref "JP1") (pin "4") (pinfunction "4_4") (pintype "passive"))
      (node (ref "R4") (pin "1") (pinfunction "1_1") (pintype "passive"))
    )
    (net (code "109") (name "Net-(JP1-Pad5)") (class "Default")
      (node (ref "JP1") (pin "5") (pinfunction "5_5") (pintype "passive"))
      (node (ref "R5") (pin "1") (pinfunction "1_1") (pintype "passive"))
    )
    (net (code "110") (name "Net-(JP1-Pad6)") (class "Default")
      (node (ref "JP1") (pin "6") (pinfunction "6_6") (pintype "passive"))
      (node (ref "R6") (pin "1") (pinfunction "1_1") (pintype "passive"))
    )
    (net (code "111") (name "Net-(JP1-Pad7)") (class "Default")
      (node (ref "JP1") (pin "7") (pinfunction "7_7") (pintype "passive"))
      (node (ref "R7") (pin "1") (pinfunction "1_1") (pintype "passive"))
    )
    (net (code "112") (name "Net-(JP1-Pad8)") (class "Default")
      (node (ref "JP1") (pin "8") (pinfunction "8_8") (pintype "passive"))
      (node (ref "R8") (pin "1") (pinfunction "1_1") (pintype "passive"))
    )
    (net (code "113") (name "VCC") (class "Default")
      (node (ref "IC1") (pin "30") (pinfunction "CS2_30") (pintype "input"))
      (node (ref "IC1") (pin "32") (pinfunction "VCC_32") (pintype "power_in"))
      (node (ref "IC10") (pin "14") (pinfunction "VCC_14") (pintype "power_in"))
      (node (ref "IC11") (pin "14") (pinfunction "VCC_14") (pintype "power_in"))
      (node (ref "IC12") (pin "20") (pinfunction "VCC_20") (pintype "power_in"))
      (node (ref "IC15") (pin "16") (pinfunction "VCC_16") (pintype "power_in"))
      (node (ref "IC16") (pin "16") (pinfunction "VCC_16") (pintype "power_in"))
      (node (ref "IC17") (pin "14") (pinfunction "VCC_14") (pintype "power_in"))
      (node (ref "IC18") (pin "14") (pinfunction "VCC_14") (pintype "power_in"))
      (node (ref "IC19") (pin "14") (pinfunction "VCC_14") (pintype "power_in"))
      (node (ref "IC2") (pin "30") (pinfunction "CS2_30") (pintype "input"))
      (node (ref "IC2") (pin "32") (pinfunction "VCC_32") (pintype "power_in"))
      (node (ref "IC3") (pin "20") (pinfunction "VCC_20") (pintype "power_in"))
      (node (ref "IC4") (pin "20") (pinfunction "VCC_20") (pintype "power_in"))
      (node (ref "IC5") (pin "16") (pinfunction "VCC_16") (pintype "power_in"))
      (node (ref "IC6") (pin "16") (pinfunction "VCC_16") (pintype "power_in"))
      (node (ref "IC9") (pin "16") (pinfunction "VCC_16") (pintype "power_in"))
      (node (ref "JP7") (pin "1") (pinfunction "1_1") (pintype "passive"))
    )
    (net (code "114") (name "unconnected-(IC7A-4A-Pad14)") (class "Default")
      (node (ref "IC7") (pin "14") (pinfunction "4A_14") (pintype "input"))
    )
    (net (code "115") (name "unconnected-(IC7A-4B-Pad13)") (class "Default")
      (node (ref "IC7") (pin "13") (pinfunction "4B_13") (pintype "input"))
    )
    (net (code "116") (name "unconnected-(IC7A-4Y-Pad12)") (class "Default")
      (node (ref "IC7") (pin "12") (pinfunction "4Y_12") (pintype "output"))
    )
  )
)
